# Power.net
KiCad netlist of a schematic drawn in Altium Designer
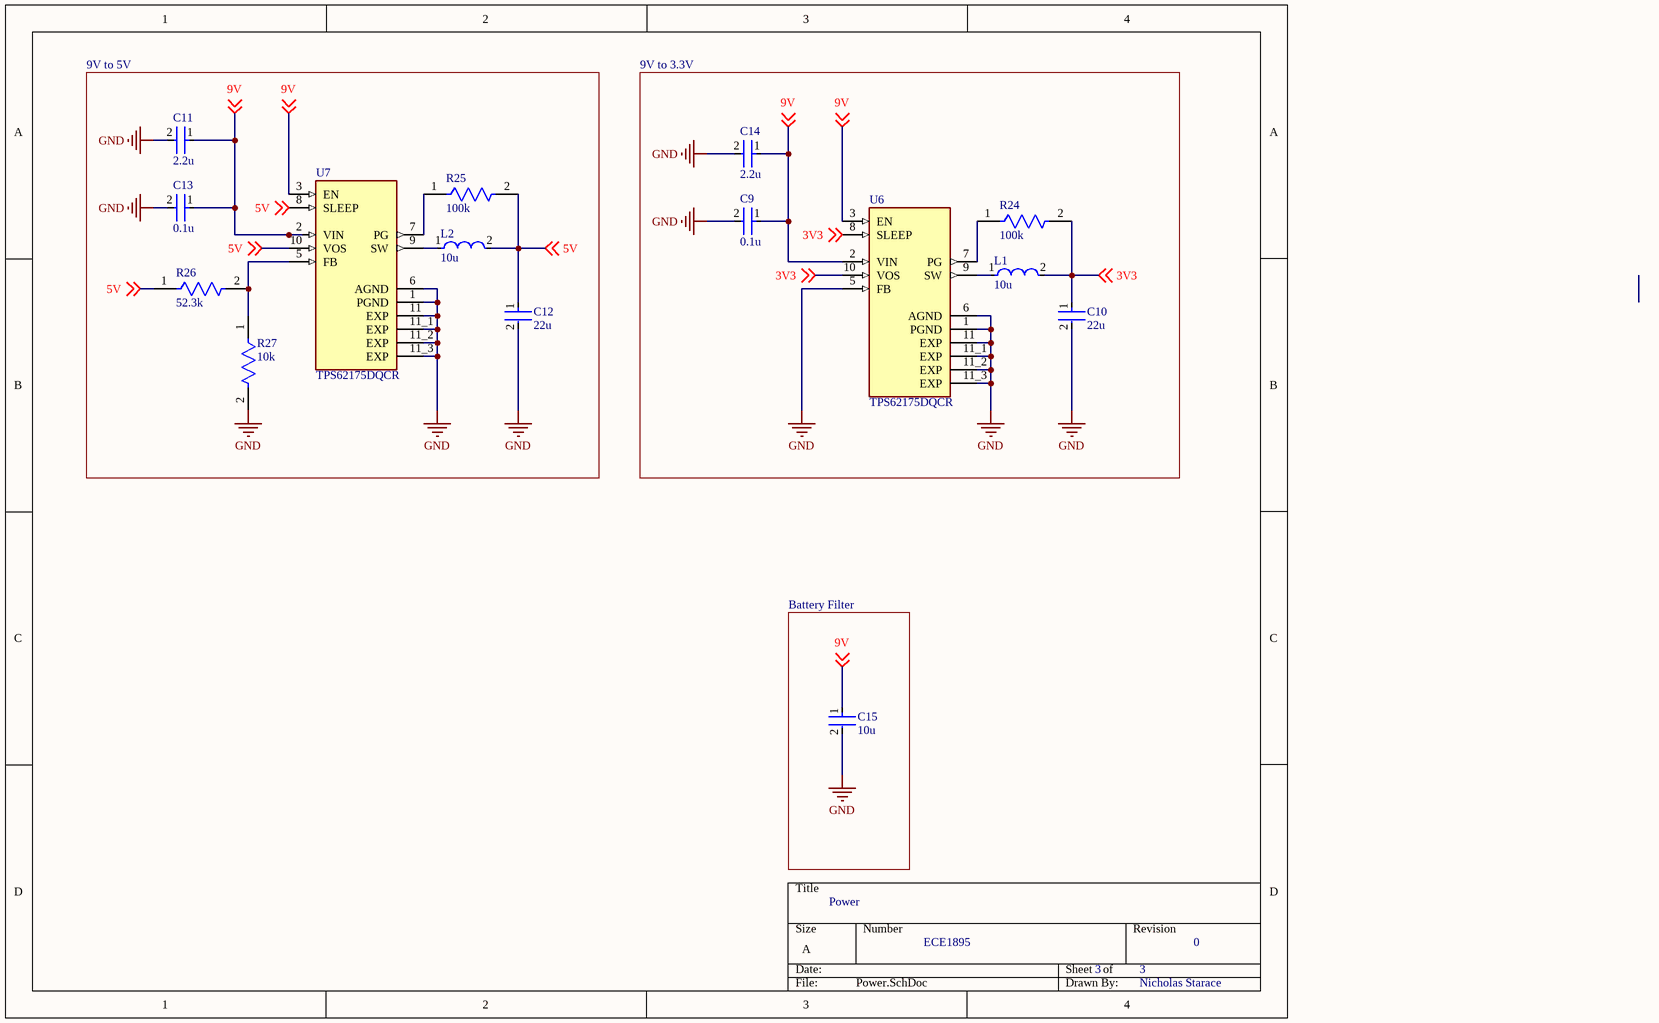
[diagram p0: Power.SchDoc]

(export (version "E")
  (design (tool "Eeschema 10.0.6"))
  (components
    (comp (ref "C9")
      (value "0.1u")
      (footprint "FP-GRM21B-0_2-e0_2_0_7-IPC_B")
      (description "CAP CER 2.2UF 100V X7T 0805")
      (libsource (lib "Altium Content Vault") (part "b4654b650e69147ec39a6b967a45e02"))
    )
    (comp (ref "C10")
      (value "22u")
      (footprint "FP-GRM21B-0_2-e0_2_0_7-IPC_B")
      (description "CAP CER 2.2UF 100V X7T 0805")
      (libsource (lib "Altium Content Vault") (part "b4654b650e69147ec39a6b967a45e02"))
    )
    (comp (ref "C11")
      (value "2.2u")
      (footprint "FP-GRM21B-0_2-e0_2_0_7-IPC_B")
      (description "CAP CER 2.2UF 100V X7T 0805")
      (libsource (lib "Altium Content Vault") (part "b4654b650e69147ec39a6b967a45e02"))
    )
    (comp (ref "C12")
      (value "22u")
      (footprint "FP-GRM21B-0_2-e0_2_0_7-IPC_B")
      (description "CAP CER 2.2UF 100V X7T 0805")
      (libsource (lib "Altium Content Vault") (part "b4654b650e69147ec39a6b967a45e02"))
    )
    (comp (ref "C13")
      (value "0.1u")
      (footprint "FP-GRM21B-0_2-e0_2_0_7-IPC_B")
      (description "CAP CER 2.2UF 100V X7T 0805")
      (libsource (lib "Altium Content Vault") (part "b4654b650e69147ec39a6b967a45e02"))
    )
    (comp (ref "C14")
      (value "2.2u")
      (footprint "FP-GRM21B-0_2-e0_2_0_7-IPC_B")
      (description "CAP CER 2.2UF 100V X7T 0805")
      (libsource (lib "Altium Content Vault") (part "b4654b650e69147ec39a6b967a45e02"))
    )
    (comp (ref "C15")
      (value "10u")
      (footprint "FP-GRM21B-0_2-e0_2_0_7-IPC_B")
      (description "CAP CER 2.2UF 100V X7T 0805")
      (libsource (lib "Altium Content Vault") (part "b4654b650e69147ec39a6b967a45e02"))
    )
    (comp (ref "L1")
      (value "10u")
      (footprint "FP-LQM21DN_70-MFG")
      (description "LQM21DN330M70L Multilayer Inductor, 33 µH, 2.99 ohm, 16 MHz, 200 mA, 0805 [2012 Metric], LQM")
      (fields (field (name "TOLERANCE") "20%"))
      (libsource (lib "Altium Content Vault") (part "725321dda6339637d4d059423bc1c3c"))
    )
    (comp (ref "L2")
      (value "10u")
      (footprint "FP-LQM21DN_70-MFG")
      (description "LQM21DN330M70L Multilayer Inductor, 33 µH, 2.99 ohm, 16 MHz, 200 mA, 0805 [2012 Metric], LQM")
      (fields (field (name "TOLERANCE") "20%"))
      (libsource (lib "Altium Content Vault") (part "725321dda6339637d4d059423bc1c3c"))
    )
    (comp (ref "R24")
      (value "100k")
      (footprint "FP-TFCR0805-MFG")
      (description "RES Thin Film,  1.72kΩ, 1%, 0.125W, 25ppm/°C, 0805")
      (libsource (lib "Altium Content Vault") (part "1029c3af85768c4190bb7ad29bc67b5"))
    )
    (comp (ref "R25")
      (value "100k")
      (footprint "FP-TFCR0805-MFG")
      (description "RES Thin Film,  1.72kΩ, 1%, 0.125W, 25ppm/°C, 0805")
      (libsource (lib "Altium Content Vault") (part "1029c3af85768c4190bb7ad29bc67b5"))
    )
    (comp (ref "R26")
      (value "52.3k")
      (footprint "FP-TFCR0805-MFG")
      (description "RES Thin Film,  1.72kΩ, 1%, 0.125W, 25ppm/°C, 0805")
      (libsource (lib "Altium Content Vault") (part "1029c3af85768c4190bb7ad29bc67b5"))
    )
    (comp (ref "R27")
      (value "10k")
      (footprint "FP-TFCR0805-MFG")
      (description "RES Thin Film,  1.72kΩ, 1%, 0.125W, 25ppm/°C, 0805")
      (libsource (lib "Altium Content Vault") (part "1029c3af85768c4190bb7ad29bc67b5"))
    )
    (comp (ref "U6")
      (value "TPS62175DQCR")
      (footprint "SON50P300X200X80-11N240X84")
      (description "28V, 0.5A Step-Down Converter with SNOOZE Mode 10-WSON -40 to 85")
      (fields (field (name "MF") "Texas Instruments"))
      (libsource (lib "TPS62175DQCR") (part "TPS62175DQCR"))
    )
    (comp (ref "U7")
      (value "TPS62175DQCR")
      (footprint "SON50P300X200X80-11N240X84")
      (description "28V, 0.5A Step-Down Converter with SNOOZE Mode 10-WSON -40 to 85")
      (fields (field (name "MF") "Texas Instruments"))
      (libsource (lib "TPS62175DQCR") (part "TPS62175DQCR"))
    )
  )
  (nets
    (net (code "1") (name "3V3") (class "Default")
      (node (ref "C10") (pin "1") (pinfunction "1_1") (pintype "passive"))
      (node (ref "L1") (pin "2") (pinfunction "2_2") (pintype "passive"))
      (node (ref "R24") (pin "2") (pinfunction "2_2") (pintype "passive"))
      (node (ref "U6") (pin "10") (pinfunction "VOS_10") (pintype "input"))
      (node (ref "U6") (pin "8") (pinfunction "SLEEP_8") (pintype "input"))
    )
    (net (code "2") (name "5V") (class "Default")
      (node (ref "C12") (pin "1") (pinfunction "1_1") (pintype "passive"))
      (node (ref "L2") (pin "2") (pinfunction "2_2") (pintype "passive"))
      (node (ref "R25") (pin "2") (pinfunction "2_2") (pintype "passive"))
      (node (ref "R26") (pin "1") (pinfunction "1_1") (pintype "passive"))
      (node (ref "U7") (pin "10") (pinfunction "VOS_10") (pintype "input"))
      (node (ref "U7") (pin "8") (pinfunction "SLEEP_8") (pintype "input"))
    )
    (net (code "3") (name "9V") (class "Default")
      (node (ref "C11") (pin "1") (pinfunction "1_1") (pintype "passive"))
      (node (ref "C13") (pin "1") (pinfunction "1_1") (pintype "passive"))
      (node (ref "C14") (pin "1") (pinfunction "1_1") (pintype "passive"))
      (node (ref "C15") (pin "1") (pinfunction "1_1") (pintype "passive"))
      (node (ref "C9") (pin "1") (pinfunction "1_1") (pintype "passive"))
      (node (ref "U6") (pin "2") (pinfunction "VIN_2") (pintype "input"))
      (node (ref "U6") (pin "3") (pinfunction "EN_3") (pintype "input"))
      (node (ref "U7") (pin "2") (pinfunction "VIN_2") (pintype "input"))
      (node (ref "U7") (pin "3") (pinfunction "EN_3") (pintype "input"))
    )
    (net (code "4") (name "GND") (class "Default")
      (node (ref "C10") (pin "2") (pinfunction "2_2") (pintype "passive"))
      (node (ref "C11") (pin "2") (pinfunction "2_2") (pintype "passive"))
      (node (ref "C12") (pin "2") (pinfunction "2_2") (pintype "passive"))
      (node (ref "C13") (pin "2") (pinfunction "2_2") (pintype "passive"))
      (node (ref "C14") (pin "2") (pinfunction "2_2") (pintype "passive"))
      (node (ref "C15") (pin "2") (pinfunction "2_2") (pintype "passive"))
      (node (ref "C9") (pin "2") (pinfunction "2_2") (pintype "passive"))
      (node (ref "R27") (pin "2") (pinfunction "2_2") (pintype "passive"))
      (node (ref "U6") (pin "1") (pinfunction "PGND_1") (pintype "power_in"))
      (node (ref "U6") (pin "11") (pinfunction "EXP_11") (pintype "power_in"))
      (node (ref "U6") (pin "11_1") (pinfunction "EXP_11_1") (pintype "power_in"))
      (node (ref "U6") (pin "11_2") (pinfunction "EXP_11_2") (pintype "power_in"))
      (node (ref "U6") (pin "11_3") (pinfunction "EXP_11_3") (pintype "power_in"))
      (node (ref "U6") (pin "5") (pinfunction "FB_5") (pintype "input"))
      (node (ref "U6") (pin "6") (pinfunction "AGND_6") (pintype "power_in"))
      (node (ref "U7") (pin "1") (pinfunction "PGND_1") (pintype "power_in"))
      (node (ref "U7") (pin "11") (pinfunction "EXP_11") (pintype "power_in"))
      (node (ref "U7") (pin "11_1") (pinfunction "EXP_11_1") (pintype "power_in"))
      (node (ref "U7") (pin "11_2") (pinfunction "EXP_11_2") (pintype "power_in"))
      (node (ref "U7") (pin "11_3") (pinfunction "EXP_11_3") (pintype "power_in"))
      (node (ref "U7") (pin "6") (pinfunction "AGND_6") (pintype "power_in"))
    )
    (net (code "5") (name "Net-(U6-PG)") (class "Default")
      (node (ref "R24") (pin "1") (pinfunction "1_1") (pintype "passive"))
      (node (ref "U6") (pin "7") (pinfunction "PG_7") (pintype "output"))
    )
    (net (code "6") (name "Net-(U6-SW)") (class "Default")
      (node (ref "L1") (pin "1") (pinfunction "1_1") (pintype "passive"))
      (node (ref "U6") (pin "9") (pinfunction "SW_9") (pintype "output"))
    )
    (net (code "7") (name "Net-(U7-FB)") (class "Default")
      (node (ref "R26") (pin "2") (pinfunction "2_2") (pintype "passive"))
      (node (ref "R27") (pin "1") (pinfunction "1_1") (pintype "passive"))
      (node (ref "U7") (pin "5") (pinfunction "FB_5") (pintype "input"))
    )
    (net (code "8") (name "Net-(U7-PG)") (class "Default")
      (node (ref "R25") (pin "1") (pinfunction "1_1") (pintype "passive"))
      (node (ref "U7") (pin "7") (pinfunction "PG_7") (pintype "output"))
    )
    (net (code "9") (name "Net-(U7-SW)") (class "Default")
      (node (ref "L2") (pin "1") (pinfunction "1_1") (pintype "passive"))
      (node (ref "U7") (pin "9") (pinfunction "SW_9") (pintype "output"))
    )
  )
)
